# AIAO.net
KiCad netlist of a schematic drawn in Altium Designer
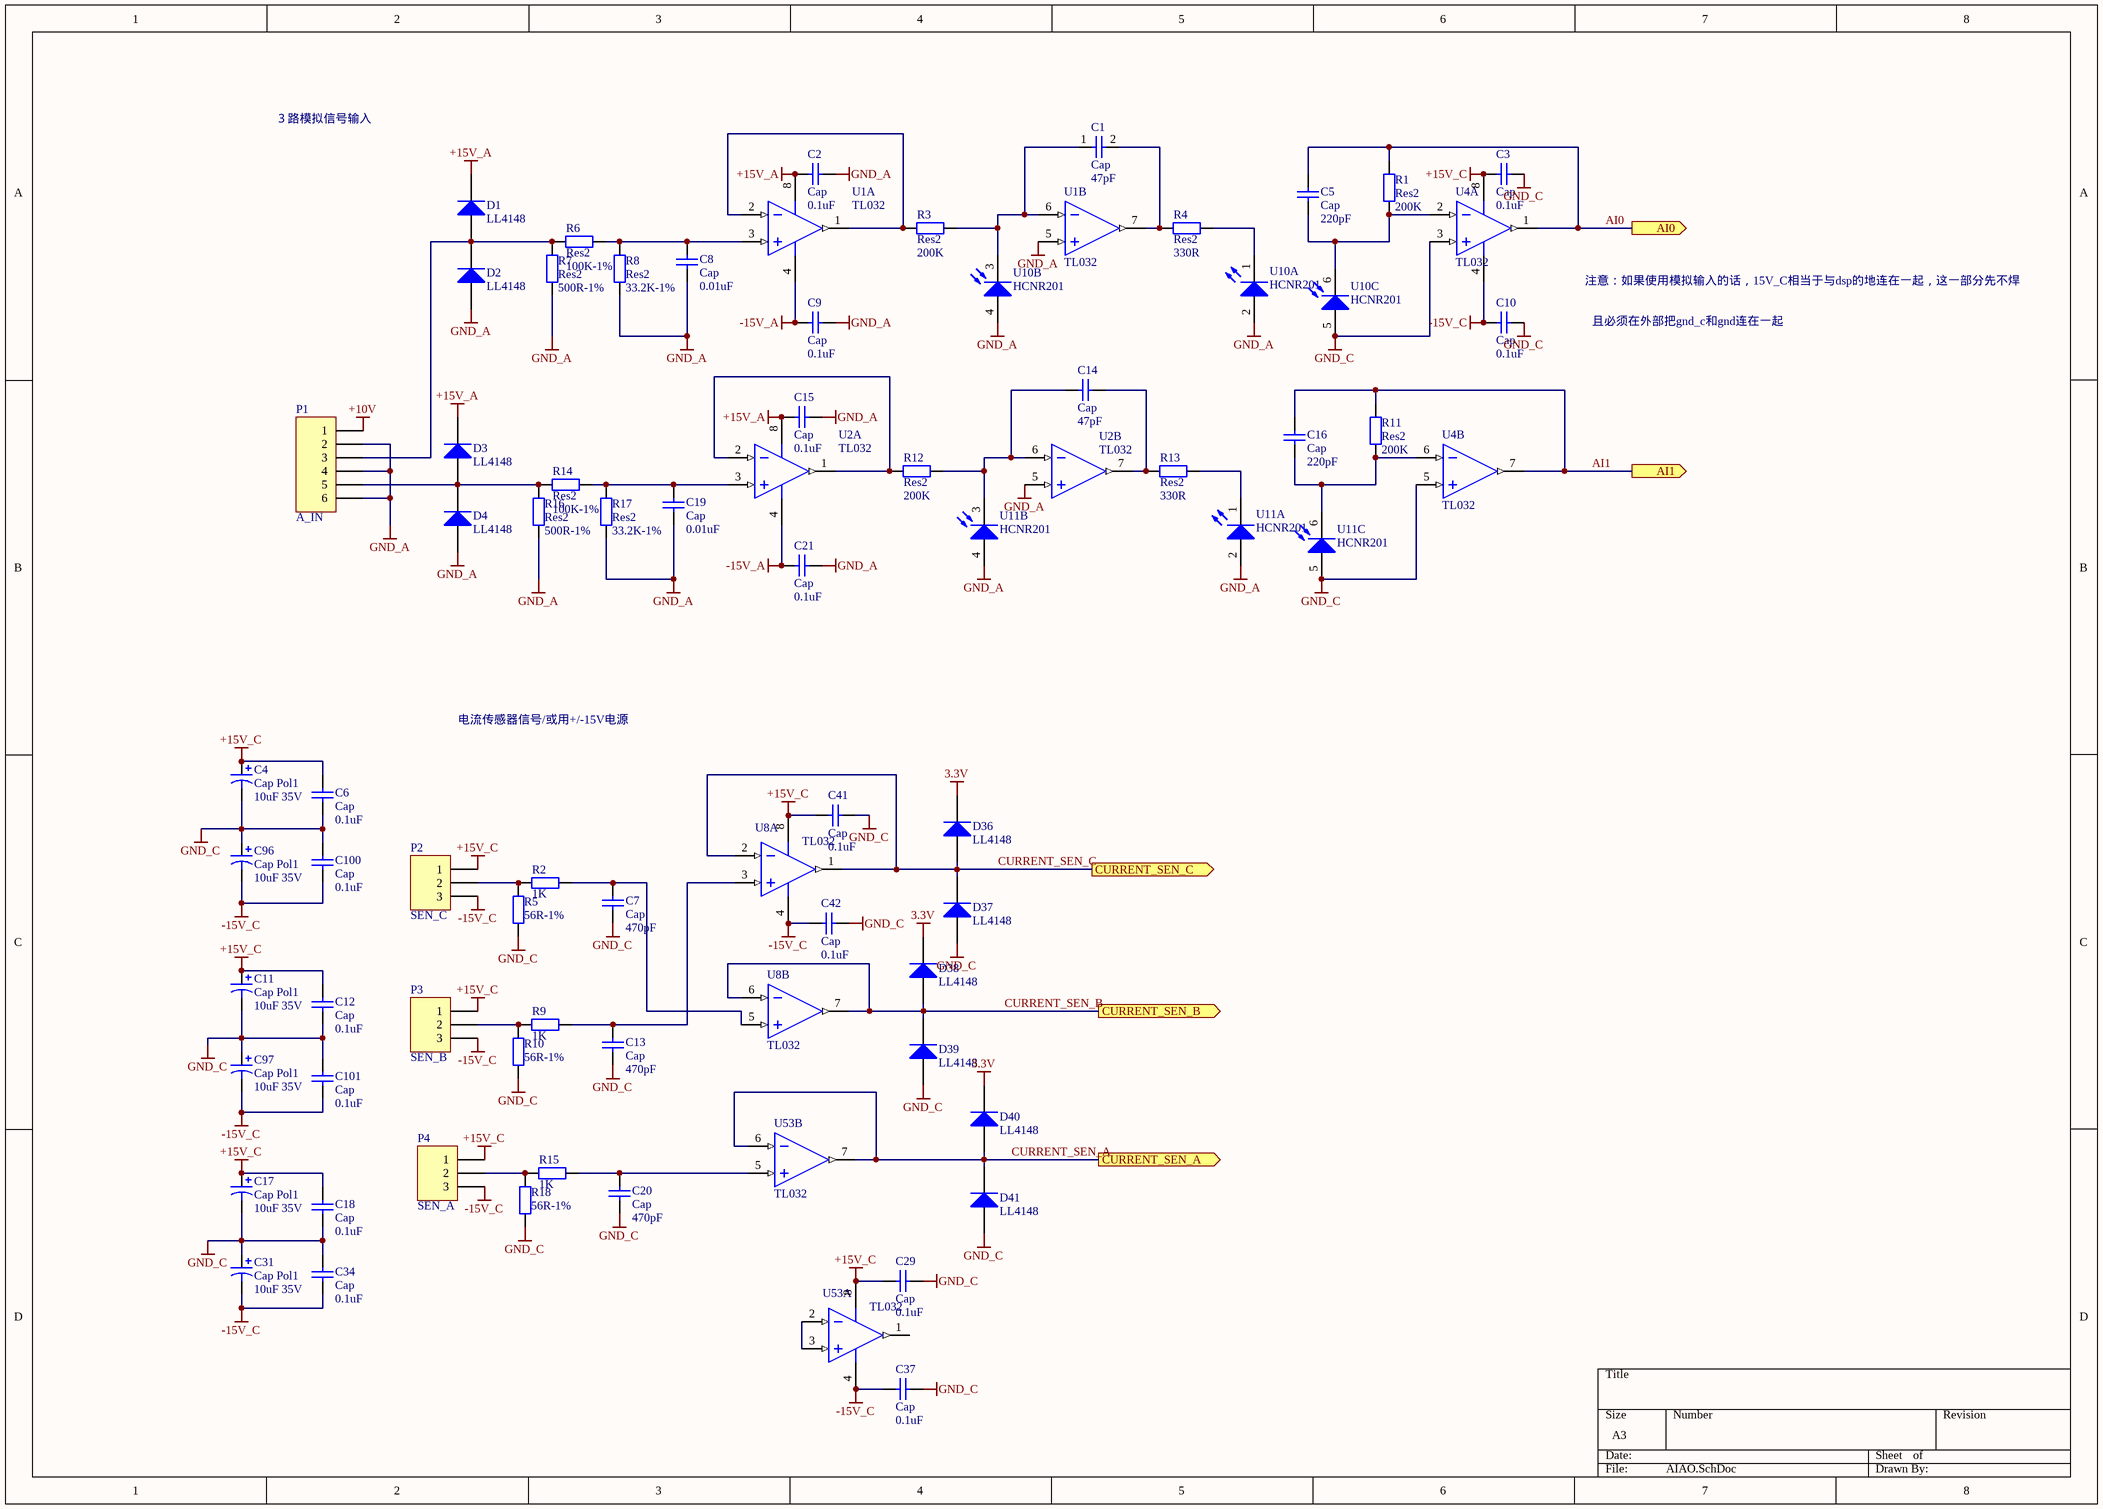
[diagram p0: AIAO.SchDoc]

(export (version "E")
  (design (tool "Eeschema 10.0.6"))
  (components
    (comp (ref "C1")
      (value "Cap")
      (footprint "1206")
      (description "Capacitor")
      (fields (field (name "ALTIUM_VALUE") "47pF") (field (name "PUBLISHER") "Altium Limited"))
      (libsource (lib "") (part "Cap_1"))
    )
    (comp (ref "C2")
      (value "Cap")
      (footprint "1206")
      (description "Capacitor")
      (fields (field (name "ALTIUM_VALUE") "0.1uF") (field (name "PUBLISHER") "Altium Limited"))
      (libsource (lib "Miscellaneous Devices") (part "Cap"))
    )
    (comp (ref "C3")
      (value "Cap")
      (footprint "1206")
      (description "Capacitor")
      (fields (field (name "ALTIUM_VALUE") "0.1uF") (field (name "PUBLISHER") "Altium Limited"))
      (libsource (lib "Miscellaneous Devices") (part "Cap"))
    )
    (comp (ref "C4")
      (value "Cap Pol1")
      (footprint "KEMET Electronics Footprints:1206")
      (description "Polarized Capacitor (Radial)")
      (fields (field (name "ALTIUM_VALUE") "10uF 35V") (field (name "PUBLISHER") "Altium Limited"))
      (libsource (lib "Miscellaneous Devices") (part "Cap Pol1"))
    )
    (comp (ref "C5")
      (value "Cap")
      (footprint "1206")
      (description "Capacitor")
      (fields (field (name "ALTIUM_VALUE") "220pF") (field (name "PUBLISHER") "Altium Limited"))
      (libsource (lib "Miscellaneous Devices") (part "Cap"))
    )
    (comp (ref "C6")
      (value "Cap")
      (footprint "1206")
      (description "Capacitor")
      (fields (field (name "ALTIUM_VALUE") "0.1uF") (field (name "PUBLISHER") "Altium Limited"))
      (libsource (lib "Miscellaneous Devices") (part "Cap"))
    )
    (comp (ref "C7")
      (value "Cap")
      (footprint "1206")
      (description "Capacitor")
      (fields (field (name "ALTIUM_VALUE") "470pF") (field (name "PUBLISHER") "Altium Limited"))
      (libsource (lib "Miscellaneous Devices") (part "Cap"))
    )
    (comp (ref "C8")
      (value "Cap")
      (footprint "1206")
      (description "Capacitor")
      (fields (field (name "ALTIUM_VALUE") "0.01uF") (field (name "PUBLISHER") "Altium Limited"))
      (libsource (lib "Miscellaneous Devices") (part "Cap"))
    )
    (comp (ref "C9")
      (value "Cap")
      (footprint "1206")
      (description "Capacitor")
      (fields (field (name "ALTIUM_VALUE") "0.1uF") (field (name "PUBLISHER") "Altium Limited"))
      (libsource (lib "Miscellaneous Devices") (part "Cap"))
    )
    (comp (ref "C10")
      (value "Cap")
      (footprint "1206")
      (description "Capacitor")
      (fields (field (name "ALTIUM_VALUE") "0.1uF") (field (name "PUBLISHER") "Altium Limited"))
      (libsource (lib "Miscellaneous Devices") (part "Cap"))
    )
    (comp (ref "C11")
      (value "Cap Pol1")
      (footprint "KEMET Electronics Footprints:1206")
      (description "Polarized Capacitor (Radial)")
      (fields (field (name "ALTIUM_VALUE") "10uF 35V") (field (name "PUBLISHER") "Altium Limited"))
      (libsource (lib "Miscellaneous Devices") (part "Cap Pol1"))
    )
    (comp (ref "C12")
      (value "Cap")
      (footprint "1206")
      (description "Capacitor")
      (fields (field (name "ALTIUM_VALUE") "0.1uF") (field (name "PUBLISHER") "Altium Limited"))
      (libsource (lib "Miscellaneous Devices") (part "Cap"))
    )
    (comp (ref "C13")
      (value "Cap")
      (footprint "1206")
      (description "Capacitor")
      (fields (field (name "ALTIUM_VALUE") "470pF") (field (name "PUBLISHER") "Altium Limited"))
      (libsource (lib "Miscellaneous Devices") (part "Cap"))
    )
    (comp (ref "C14")
      (value "Cap")
      (footprint "1206")
      (description "Capacitor")
      (fields (field (name "ALTIUM_VALUE") "47pF") (field (name "PUBLISHER") "Altium Limited"))
      (libsource (lib "Miscellaneous Devices") (part "Cap"))
    )
    (comp (ref "C15")
      (value "Cap")
      (footprint "1206")
      (description "Capacitor")
      (fields (field (name "ALTIUM_VALUE") "0.1uF") (field (name "PUBLISHER") "Altium Limited"))
      (libsource (lib "Miscellaneous Devices") (part "Cap"))
    )
    (comp (ref "C16")
      (value "Cap")
      (footprint "1206")
      (description "Capacitor")
      (fields (field (name "ALTIUM_VALUE") "220pF") (field (name "PUBLISHER") "Altium Limited"))
      (libsource (lib "Miscellaneous Devices") (part "Cap"))
    )
    (comp (ref "C17")
      (value "Cap Pol1")
      (footprint "KEMET Electronics Footprints:1206")
      (description "Polarized Capacitor (Radial)")
      (fields (field (name "ALTIUM_VALUE") "10uF 35V") (field (name "PUBLISHER") "Altium Limited"))
      (libsource (lib "Miscellaneous Devices") (part "Cap Pol1"))
    )
    (comp (ref "C18")
      (value "Cap")
      (footprint "1206")
      (description "Capacitor")
      (fields (field (name "ALTIUM_VALUE") "0.1uF") (field (name "PUBLISHER") "Altium Limited"))
      (libsource (lib "Miscellaneous Devices") (part "Cap"))
    )
    (comp (ref "C19")
      (value "Cap")
      (footprint "1206")
      (description "Capacitor")
      (fields (field (name "ALTIUM_VALUE") "0.01uF") (field (name "PUBLISHER") "Altium Limited"))
      (libsource (lib "Miscellaneous Devices") (part "Cap"))
    )
    (comp (ref "C20")
      (value "Cap")
      (footprint "1206")
      (description "Capacitor")
      (fields (field (name "ALTIUM_VALUE") "470pF") (field (name "PUBLISHER") "Altium Limited"))
      (libsource (lib "Miscellaneous Devices") (part "Cap"))
    )
    (comp (ref "C21")
      (value "Cap")
      (footprint "1206")
      (description "Capacitor")
      (fields (field (name "ALTIUM_VALUE") "0.1uF") (field (name "PUBLISHER") "Altium Limited"))
      (libsource (lib "Miscellaneous Devices") (part "Cap"))
    )
    (comp (ref "C29")
      (value "Cap")
      (footprint "1206")
      (description "Capacitor")
      (fields (field (name "ALTIUM_VALUE") "0.1uF") (field (name "PUBLISHER") "Altium Limited"))
      (libsource (lib "Miscellaneous Devices") (part "Cap"))
    )
    (comp (ref "C31")
      (value "Cap Pol1")
      (footprint "KEMET Electronics Footprints:1206")
      (description "Polarized Capacitor (Radial)")
      (fields (field (name "ALTIUM_VALUE") "10uF 35V") (field (name "PUBLISHER") "Altium Limited"))
      (libsource (lib "Miscellaneous Devices") (part "Cap Pol1"))
    )
    (comp (ref "C34")
      (value "Cap")
      (footprint "1206")
      (description "Capacitor")
      (fields (field (name "ALTIUM_VALUE") "0.1uF") (field (name "PUBLISHER") "Altium Limited"))
      (libsource (lib "Miscellaneous Devices") (part "Cap"))
    )
    (comp (ref "C37")
      (value "Cap")
      (footprint "1206")
      (description "Capacitor")
      (fields (field (name "ALTIUM_VALUE") "0.1uF") (field (name "PUBLISHER") "Altium Limited"))
      (libsource (lib "Miscellaneous Devices") (part "Cap"))
    )
    (comp (ref "C41")
      (value "Cap")
      (footprint "1206")
      (description "Capacitor")
      (fields (field (name "ALTIUM_VALUE") "0.1uF") (field (name "PUBLISHER") "Altium Limited"))
      (libsource (lib "Miscellaneous Devices") (part "Cap"))
    )
    (comp (ref "C42")
      (value "Cap")
      (footprint "1206")
      (description "Capacitor")
      (fields (field (name "ALTIUM_VALUE") "0.1uF") (field (name "PUBLISHER") "Altium Limited"))
      (libsource (lib "Miscellaneous Devices") (part "Cap"))
    )
    (comp (ref "C96")
      (value "Cap Pol1")
      (footprint "KEMET Electronics Footprints:1206")
      (description "Polarized Capacitor (Radial)")
      (fields (field (name "ALTIUM_VALUE") "10uF 35V") (field (name "PUBLISHER") "Altium Limited"))
      (libsource (lib "Miscellaneous Devices") (part "Cap Pol1"))
    )
    (comp (ref "C97")
      (value "Cap Pol1")
      (footprint "KEMET Electronics Footprints:1206")
      (description "Polarized Capacitor (Radial)")
      (fields (field (name "ALTIUM_VALUE") "10uF 35V") (field (name "PUBLISHER") "Altium Limited"))
      (libsource (lib "Miscellaneous Devices") (part "Cap Pol1"))
    )
    (comp (ref "C100")
      (value "Cap")
      (footprint "1206")
      (description "Capacitor")
      (fields (field (name "ALTIUM_VALUE") "0.1uF") (field (name "PUBLISHER") "Altium Limited"))
      (libsource (lib "Miscellaneous Devices") (part "Cap"))
    )
    (comp (ref "C101")
      (value "Cap")
      (footprint "1206")
      (description "Capacitor")
      (fields (field (name "ALTIUM_VALUE") "0.1uF") (field (name "PUBLISHER") "Altium Limited"))
      (libsource (lib "Miscellaneous Devices") (part "Cap"))
    )
    (comp (ref "D1")
      (value "LL4148")
      (footprint "SOD-80/MLL34")
      (description "High Conductance Fast Diode")
      (fields (field (name "PUBLISHER") "Altium Limited"))
      (libsource (lib "Miscellaneous Devices") (part "Diode 1N4148"))
    )
    (comp (ref "D2")
      (value "LL4148")
      (footprint "SOD-80/MLL34")
      (description "High Conductance Fast Diode")
      (fields (field (name "PUBLISHER") "Altium Limited"))
      (libsource (lib "Miscellaneous Devices") (part "Diode 1N4148"))
    )
    (comp (ref "D3")
      (value "LL4148")
      (footprint "SOD-80/MLL34")
      (description "High Conductance Fast Diode")
      (fields (field (name "PUBLISHER") "Altium Limited"))
      (libsource (lib "Miscellaneous Devices") (part "Diode 1N4148"))
    )
    (comp (ref "D4")
      (value "LL4148")
      (footprint "SOD-80/MLL34")
      (description "High Conductance Fast Diode")
      (fields (field (name "PUBLISHER") "Altium Limited"))
      (libsource (lib "Miscellaneous Devices") (part "Diode 1N4148"))
    )
    (comp (ref "D36")
      (value "LL4148")
      (footprint "SOD-80/MLL34")
      (description "1 Amp General Purpose Rectifier")
      (fields (field (name "PUBLISHER") "Altium Limited"))
      (libsource (lib "Miscellaneous Devices") (part "Diode 1N4007"))
    )
    (comp (ref "D37")
      (value "LL4148")
      (footprint "SOD-80/MLL34")
      (description "1 Amp General Purpose Rectifier")
      (fields (field (name "PUBLISHER") "Altium Limited"))
      (libsource (lib "Miscellaneous Devices") (part "Diode 1N4007"))
    )
    (comp (ref "D38")
      (value "LL4148")
      (footprint "SOD-80/MLL34")
      (description "1 Amp General Purpose Rectifier")
      (fields (field (name "PUBLISHER") "Altium Limited"))
      (libsource (lib "Miscellaneous Devices") (part "Diode 1N4007"))
    )
    (comp (ref "D39")
      (value "LL4148")
      (footprint "SOD-80/MLL34")
      (description "1 Amp General Purpose Rectifier")
      (fields (field (name "PUBLISHER") "Altium Limited"))
      (libsource (lib "Miscellaneous Devices") (part "Diode 1N4007"))
    )
    (comp (ref "D40")
      (value "LL4148")
      (footprint "SOD-80/MLL34")
      (description "1 Amp General Purpose Rectifier")
      (fields (field (name "PUBLISHER") "Altium Limited"))
      (libsource (lib "Miscellaneous Devices") (part "Diode 1N4007"))
    )
    (comp (ref "D41")
      (value "LL4148")
      (footprint "SOD-80/MLL34")
      (description "1 Amp General Purpose Rectifier")
      (fields (field (name "PUBLISHER") "Altium Limited"))
      (libsource (lib "Miscellaneous Devices") (part "Diode 1N4007"))
    )
    (comp (ref "P1")
      (value "A_IN")
      (footprint "phenox-6")
      (description "Header, 6-Pin")
      (fields (field (name "PUBLISHER") "Altium Limited"))
      (libsource (lib "Miscellaneous Connectors") (part "Header 6"))
    )
    (comp (ref "P2")
      (value "SEN_C")
      (footprint "PHENOX-3")
      (description "Header, 3-Pin")
      (fields (field (name "PUBLISHER") "Altium Limited"))
      (libsource (lib "Miscellaneous Connectors") (part "Header 3"))
    )
    (comp (ref "P3")
      (value "SEN_B")
      (footprint "PHENOX-3")
      (description "Header, 3-Pin")
      (fields (field (name "PUBLISHER") "Altium Limited"))
      (libsource (lib "Miscellaneous Connectors") (part "Header 3"))
    )
    (comp (ref "P4")
      (value "SEN_A")
      (footprint "PHENOX-3")
      (description "Header, 3-Pin")
      (fields (field (name "PUBLISHER") "Altium Limited"))
      (libsource (lib "Miscellaneous Connectors") (part "Header 3"))
    )
    (comp (ref "R1")
      (value "Res2")
      (footprint "1206")
      (description "Resistor")
      (fields (field (name "ALTIUM_VALUE") "200K") (field (name "PUBLISHER") "Altium Limited"))
      (libsource (lib "Miscellaneous Devices") (part "Res2"))
    )
    (comp (ref "R2")
      (value "1K")
      (footprint "1206")
      (description "Resistor")
      (fields (field (name "Comment") "Res2") (field (name "PUBLISHER") "Altium Limited"))
      (libsource (lib "") (part "Res2_1"))
    )
    (comp (ref "R3")
      (value "Res2")
      (footprint "1206")
      (description "Resistor")
      (fields (field (name "ALTIUM_VALUE") "200K") (field (name "PUBLISHER") "Altium Limited"))
      (libsource (lib "") (part "Res2_1"))
    )
    (comp (ref "R4")
      (value "Res2")
      (footprint "1206")
      (description "Resistor")
      (fields (field (name "ALTIUM_VALUE") "330R") (field (name "PUBLISHER") "Altium Limited"))
      (libsource (lib "") (part "Res2_1"))
    )
    (comp (ref "R5")
      (value "56R-1%")
      (footprint "1206")
      (description "Resistor")
      (fields (field (name "Comment") "Res2") (field (name "PUBLISHER") "Altium Limited"))
      (libsource (lib "Miscellaneous Devices") (part "Res2"))
    )
    (comp (ref "R6")
      (value "Res2")
      (footprint "1206")
      (description "Resistor")
      (fields (field (name "ALTIUM_VALUE") "100K-1%") (field (name "PUBLISHER") "Altium Limited"))
      (libsource (lib "") (part "Res2_1"))
    )
    (comp (ref "R7")
      (value "Res2")
      (footprint "1206")
      (description "Resistor")
      (fields (field (name "ALTIUM_VALUE") "500R-1%") (field (name "PUBLISHER") "Altium Limited"))
      (libsource (lib "Miscellaneous Devices") (part "Res2"))
    )
    (comp (ref "R8")
      (value "Res2")
      (footprint "1206")
      (description "Resistor")
      (fields (field (name "ALTIUM_VALUE") "33.2K-1%") (field (name "PUBLISHER") "Altium Limited"))
      (libsource (lib "Miscellaneous Devices") (part "Res2"))
    )
    (comp (ref "R9")
      (value "1K")
      (footprint "1206")
      (description "Resistor")
      (fields (field (name "Comment") "Res2") (field (name "PUBLISHER") "Altium Limited"))
      (libsource (lib "") (part "Res2_1"))
    )
    (comp (ref "R10")
      (value "56R-1%")
      (footprint "1206")
      (description "Resistor")
      (fields (field (name "Comment") "Res2") (field (name "PUBLISHER") "Altium Limited"))
      (libsource (lib "Miscellaneous Devices") (part "Res2"))
    )
    (comp (ref "R11")
      (value "Res2")
      (footprint "1206")
      (description "Resistor")
      (fields (field (name "ALTIUM_VALUE") "200K") (field (name "PUBLISHER") "Altium Limited"))
      (libsource (lib "Miscellaneous Devices") (part "Res2"))
    )
    (comp (ref "R12")
      (value "Res2")
      (footprint "1206")
      (description "Resistor")
      (fields (field (name "ALTIUM_VALUE") "200K") (field (name "PUBLISHER") "Altium Limited"))
      (libsource (lib "") (part "Res2_1"))
    )
    (comp (ref "R13")
      (value "Res2")
      (footprint "1206")
      (description "Resistor")
      (fields (field (name "ALTIUM_VALUE") "330R") (field (name "PUBLISHER") "Altium Limited"))
      (libsource (lib "") (part "Res2_1"))
    )
    (comp (ref "R14")
      (value "Res2")
      (footprint "1206")
      (description "Resistor")
      (fields (field (name "ALTIUM_VALUE") "100K-1%") (field (name "PUBLISHER") "Altium Limited"))
      (libsource (lib "") (part "Res2_1"))
    )
    (comp (ref "R15")
      (value "1K")
      (footprint "1206")
      (description "Resistor")
      (fields (field (name "Comment") "Res2") (field (name "PUBLISHER") "Altium Limited"))
      (libsource (lib "") (part "Res2_1"))
    )
    (comp (ref "R16")
      (value "Res2")
      (footprint "1206")
      (description "Resistor")
      (fields (field (name "ALTIUM_VALUE") "500R-1%") (field (name "PUBLISHER") "Altium Limited"))
      (libsource (lib "Miscellaneous Devices") (part "Res2"))
    )
    (comp (ref "R17")
      (value "Res2")
      (footprint "1206")
      (description "Resistor")
      (fields (field (name "ALTIUM_VALUE") "33.2K-1%") (field (name "PUBLISHER") "Altium Limited"))
      (libsource (lib "Miscellaneous Devices") (part "Res2"))
    )
    (comp (ref "R18")
      (value "56R-1%")
      (footprint "1206")
      (description "Resistor")
      (fields (field (name "Comment") "Res2") (field (name "PUBLISHER") "Altium Limited"))
      (libsource (lib "Miscellaneous Devices") (part "Res2"))
    )
    (comp (ref "U1") (value "TL032") (footprint "SO-8") (libsource (lib "Schlib1") (part "TL032")))
    (comp (ref "U2") (value "TL032") (footprint "SO-8") (libsource (lib "Schlib1") (part "TL032")))
    (comp (ref "U4") (value "TL032") (footprint "SO-8") (libsource (lib "Schlib1") (part "TL032")))
    (comp (ref "U8") (value "TL032") (footprint "SO-8") (libsource (lib "Schlib1") (part "TL032")))
    (comp (ref "U10")
      (value "HCNR201")
      (footprint "SOP254P1230X400-8N-2")
      (libsource (lib "Schlib2") (part "HCNR201"))
    )
    (comp (ref "U11")
      (value "HCNR201")
      (footprint "SOP254P1230X400-8N-2")
      (libsource (lib "Schlib2") (part "HCNR201"))
    )
    (comp (ref "U53") (value "TL032") (footprint "SO-8") (libsource (lib "Schlib1") (part "TL032")))
  )
  (nets
    (net (code "1") (name "+10V") (class "Default")
      (node (ref "P1") (pin "1") (pinfunction "1_1") (pintype "passive"))
    )
    (net (code "2") (name "+15V_A") (class "Default")
      (node (ref "C15") (pin "1") (pinfunction "1_1") (pintype "passive"))
      (node (ref "C2") (pin "1") (pinfunction "1_1") (pintype "passive"))
      (node (ref "D1") (pin "2") (pinfunction "K_2") (pintype "passive"))
      (node (ref "D3") (pin "2") (pinfunction "K_2") (pintype "passive"))
      (node (ref "U1") (pin "8") (pinfunction "V+_8") (pintype "power_in"))
      (node (ref "U2") (pin "8") (pinfunction "V+_8") (pintype "power_in"))
    )
    (net (code "3") (name "+15V_C") (class "Default")
      (node (ref "C11") (pin "1") (pinfunction "1_1") (pintype "passive"))
      (node (ref "C12") (pin "2") (pinfunction "2_2") (pintype "passive"))
      (node (ref "C17") (pin "1") (pinfunction "1_1") (pintype "passive"))
      (node (ref "C18") (pin "2") (pinfunction "2_2") (pintype "passive"))
      (node (ref "C29") (pin "2") (pinfunction "2_2") (pintype "passive"))
      (node (ref "C3") (pin "1") (pinfunction "1_1") (pintype "passive"))
      (node (ref "C4") (pin "1") (pinfunction "1_1") (pintype "passive"))
      (node (ref "C41") (pin "2") (pinfunction "2_2") (pintype "passive"))
      (node (ref "C6") (pin "2") (pinfunction "2_2") (pintype "passive"))
      (node (ref "P2") (pin "1") (pinfunction "1_1") (pintype "passive"))
      (node (ref "P3") (pin "1") (pinfunction "1_1") (pintype "passive"))
      (node (ref "P4") (pin "1") (pinfunction "1_1") (pintype "passive"))
      (node (ref "U4") (pin "8") (pinfunction "V+_8") (pintype "power_in"))
      (node (ref "U53") (pin "8") (pinfunction "V+_8") (pintype "power_in"))
      (node (ref "U8") (pin "8") (pinfunction "V+_8") (pintype "power_in"))
    )
    (net (code "4") (name "-15V_A") (class "Default")
      (node (ref "C21") (pin "1") (pinfunction "1_1") (pintype "passive"))
      (node (ref "C9") (pin "1") (pinfunction "1_1") (pintype "passive"))
      (node (ref "U1") (pin "4") (pinfunction "V-_4") (pintype "power_in"))
      (node (ref "U2") (pin "4") (pinfunction "V-_4") (pintype "power_in"))
    )
    (net (code "5") (name "-15V_C") (class "Default")
      (node (ref "C10") (pin "1") (pinfunction "1_1") (pintype "passive"))
      (node (ref "C100") (pin "1") (pinfunction "1_1") (pintype "passive"))
      (node (ref "C101") (pin "1") (pinfunction "1_1") (pintype "passive"))
      (node (ref "C31") (pin "2") (pinfunction "2_2") (pintype "passive"))
      (node (ref "C34") (pin "1") (pinfunction "1_1") (pintype "passive"))
      (node (ref "C37") (pin "2") (pinfunction "2_2") (pintype "passive"))
      (node (ref "C42") (pin "2") (pinfunction "2_2") (pintype "passive"))
      (node (ref "C96") (pin "2") (pinfunction "2_2") (pintype "passive"))
      (node (ref "C97") (pin "2") (pinfunction "2_2") (pintype "passive"))
      (node (ref "P2") (pin "3") (pinfunction "3_3") (pintype "passive"))
      (node (ref "P3") (pin "3") (pinfunction "3_3") (pintype "passive"))
      (node (ref "P4") (pin "3") (pinfunction "3_3") (pintype "passive"))
      (node (ref "U4") (pin "4") (pinfunction "V-_4") (pintype "power_in"))
      (node (ref "U53") (pin "4") (pinfunction "V-_4") (pintype "power_in"))
      (node (ref "U8") (pin "4") (pinfunction "V-_4") (pintype "power_in"))
    )
    (net (code "6") (name "/AI0") (class "Default")
      (node (ref "C5") (pin "2") (pinfunction "2_2") (pintype "passive"))
      (node (ref "R1") (pin "2") (pinfunction "2_2") (pintype "passive"))
      (node (ref "U4") (pin "1") (pinfunction "OUT_1") (pintype "output"))
    )
    (net (code "7") (name "/AI1") (class "Default")
      (node (ref "C16") (pin "2") (pinfunction "2_2") (pintype "passive"))
      (node (ref "R11") (pin "2") (pinfunction "2_2") (pintype "passive"))
      (node (ref "U4") (pin "7") (pinfunction "OUT_7") (pintype "output"))
    )
    (net (code "8") (name "/CURRENT_SEN_A") (class "Default")
      (node (ref "D40") (pin "1") (pinfunction "A_1") (pintype "passive"))
      (node (ref "D41") (pin "2") (pinfunction "K_2") (pintype "passive"))
      (node (ref "U53") (pin "6") (pinfunction "IN-_6") (pintype "input"))
      (node (ref "U53") (pin "7") (pinfunction "OUT_7") (pintype "output"))
    )
    (net (code "9") (name "/CURRENT_SEN_B") (class "Default")
      (node (ref "D38") (pin "1") (pinfunction "A_1") (pintype "passive"))
      (node (ref "D39") (pin "2") (pinfunction "K_2") (pintype "passive"))
      (node (ref "U8") (pin "6") (pinfunction "IN-_6") (pintype "input"))
      (node (ref "U8") (pin "7") (pinfunction "OUT_7") (pintype "output"))
    )
    (net (code "10") (name "/CURRENT_SEN_C") (class "Default")
      (node (ref "D36") (pin "1") (pinfunction "A_1") (pintype "passive"))
      (node (ref "D37") (pin "2") (pinfunction "K_2") (pintype "passive"))
      (node (ref "U8") (pin "1") (pinfunction "OUT_1") (pintype "output"))
      (node (ref "U8") (pin "2") (pinfunction "IN-_2") (pintype "input"))
    )
    (net (code "11") (name "3.3V") (class "Default")
      (node (ref "D36") (pin "2") (pinfunction "K_2") (pintype "passive"))
      (node (ref "D38") (pin "2") (pinfunction "K_2") (pintype "passive"))
      (node (ref "D40") (pin "2") (pinfunction "K_2") (pintype "passive"))
    )
    (net (code "12") (name "GND_A") (class "Default")
      (node (ref "C15") (pin "2") (pinfunction "2_2") (pintype "passive"))
      (node (ref "C19") (pin "1") (pinfunction "1_1") (pintype "passive"))
      (node (ref "C2") (pin "2") (pinfunction "2_2") (pintype "passive"))
      (node (ref "C21") (pin "2") (pinfunction "2_2") (pintype "passive"))
      (node (ref "C8") (pin "1") (pinfunction "1_1") (pintype "passive"))
      (node (ref "C9") (pin "2") (pinfunction "2_2") (pintype "passive"))
      (node (ref "D2") (pin "1") (pinfunction "A_1") (pintype "passive"))
      (node (ref "D4") (pin "1") (pinfunction "A_1") (pintype "passive"))
      (node (ref "P1") (pin "2") (pinfunction "2_2") (pintype "passive"))
      (node (ref "P1") (pin "4") (pinfunction "4_4") (pintype "passive"))
      (node (ref "P1") (pin "6") (pinfunction "6_6") (pintype "passive"))
      (node (ref "R16") (pin "1") (pinfunction "1_1") (pintype "passive"))
      (node (ref "R17") (pin "1") (pinfunction "1_1") (pintype "passive"))
      (node (ref "R7") (pin "1") (pinfunction "1_1") (pintype "passive"))
      (node (ref "R8") (pin "1") (pinfunction "1_1") (pintype "passive"))
      (node (ref "U1") (pin "5") (pinfunction "IN+_5") (pintype "input"))
      (node (ref "U10") (pin "2") (pinfunction "A_2") (pintype "passive"))
      (node (ref "U10") (pin "4") (pinfunction "A_4") (pintype "passive"))
      (node (ref "U11") (pin "2") (pinfunction "A_2") (pintype "passive"))
      (node (ref "U11") (pin "4") (pinfunction "A_4") (pintype "passive"))
      (node (ref "U2") (pin "5") (pinfunction "IN+_5") (pintype "input"))
    )
    (net (code "13") (name "GND_C") (class "Default")
      (node (ref "C10") (pin "2") (pinfunction "2_2") (pintype "passive"))
      (node (ref "C100") (pin "2") (pinfunction "2_2") (pintype "passive"))
      (node (ref "C101") (pin "2") (pinfunction "2_2") (pintype "passive"))
      (node (ref "C11") (pin "2") (pinfunction "2_2") (pintype "passive"))
      (node (ref "C12") (pin "1") (pinfunction "1_1") (pintype "passive"))
      (node (ref "C13") (pin "1") (pinfunction "1_1") (pintype "passive"))
      (node (ref "C17") (pin "2") (pinfunction "2_2") (pintype "passive"))
      (node (ref "C18") (pin "1") (pinfunction "1_1") (pintype "passive"))
      (node (ref "C20") (pin "1") (pinfunction "1_1") (pintype "passive"))
      (node (ref "C29") (pin "1") (pinfunction "1_1") (pintype "passive"))
      (node (ref "C3") (pin "2") (pinfunction "2_2") (pintype "passive"))
      (node (ref "C31") (pin "1") (pinfunction "1_1") (pintype "passive"))
      (node (ref "C34") (pin "2") (pinfunction "2_2") (pintype "passive"))
      (node (ref "C37") (pin "1") (pinfunction "1_1") (pintype "passive"))
      (node (ref "C4") (pin "2") (pinfunction "2_2") (pintype "passive"))
      (node (ref "C41") (pin "1") (pinfunction "1_1") (pintype "passive"))
      (node (ref "C42") (pin "1") (pinfunction "1_1") (pintype "passive"))
      (node (ref "C6") (pin "1") (pinfunction "1_1") (pintype "passive"))
      (node (ref "C7") (pin "1") (pinfunction "1_1") (pintype "passive"))
      (node (ref "C96") (pin "1") (pinfunction "1_1") (pintype "passive"))
      (node (ref "C97") (pin "1") (pinfunction "1_1") (pintype "passive"))
      (node (ref "D37") (pin "1") (pinfunction "A_1") (pintype "passive"))
      (node (ref "D39") (pin "1") (pinfunction "A_1") (pintype "passive"))
      (node (ref "D41") (pin "1") (pinfunction "A_1") (pintype "passive"))
      (node (ref "R10") (pin "1") (pinfunction "1_1") (pintype "passive"))
      (node (ref "R18") (pin "1") (pinfunction "1_1") (pintype "passive"))
      (node (ref "R5") (pin "1") (pinfunction "1_1") (pintype "passive"))
      (node (ref "U10") (pin "5") (pinfunction "A_5") (pintype "passive"))
      (node (ref "U11") (pin "5") (pinfunction "A_5") (pintype "passive"))
      (node (ref "U4") (pin "3") (pinfunction "IN+_3") (pintype "input"))
      (node (ref "U4") (pin "5") (pinfunction "IN+_5") (pintype "input"))
    )
    (net (code "14") (name "Net-(D1-A)") (class "Default")
      (node (ref "D1") (pin "1") (pinfunction "A_1") (pintype "passive"))
      (node (ref "D2") (pin "2") (pinfunction "K_2") (pintype "passive"))
      (node (ref "P1") (pin "3") (pinfunction "3_3") (pintype "passive"))
      (node (ref "R6") (pin "1") (pinfunction "1_1") (pintype "passive"))
      (node (ref "R7") (pin "2") (pinfunction "2_2") (pintype "passive"))
    )
    (net (code "15") (name "Net-(D3-A)") (class "Default")
      (node (ref "D3") (pin "1") (pinfunction "A_1") (pintype "passive"))
      (node (ref "D4") (pin "2") (pinfunction "K_2") (pintype "passive"))
      (node (ref "P1") (pin "5") (pinfunction "5_5") (pintype "passive"))
      (node (ref "R14") (pin "1") (pinfunction "1_1") (pintype "passive"))
      (node (ref "R16") (pin "2") (pinfunction "2_2") (pintype "passive"))
    )
    (net (code "16") (name "Net-(P2-Pad2)") (class "Default")
      (node (ref "P2") (pin "2") (pinfunction "2_2") (pintype "passive"))
      (node (ref "R2") (pin "1") (pinfunction "1_1") (pintype "passive"))
      (node (ref "R5") (pin "2") (pinfunction "2_2") (pintype "passive"))
    )
    (net (code "17") (name "Net-(P3-Pad2)") (class "Default")
      (node (ref "P3") (pin "2") (pinfunction "2_2") (pintype "passive"))
      (node (ref "R10") (pin "2") (pinfunction "2_2") (pintype "passive"))
      (node (ref "R9") (pin "1") (pinfunction "1_1") (pintype "passive"))
    )
    (net (code "18") (name "Net-(P4-Pad2)") (class "Default")
      (node (ref "P4") (pin "2") (pinfunction "2_2") (pintype "passive"))
      (node (ref "R15") (pin "1") (pinfunction "1_1") (pintype "passive"))
      (node (ref "R18") (pin "2") (pinfunction "2_2") (pintype "passive"))
    )
    (net (code "19") (name "Net-(U1A-IN+)") (class "Default")
      (node (ref "C8") (pin "2") (pinfunction "2_2") (pintype "passive"))
      (node (ref "R6") (pin "2") (pinfunction "2_2") (pintype "passive"))
      (node (ref "R8") (pin "2") (pinfunction "2_2") (pintype "passive"))
      (node (ref "U1") (pin "3") (pinfunction "IN+_3") (pintype "input"))
    )
    (net (code "20") (name "Net-(U1A-IN-)") (class "Default")
      (node (ref "R3") (pin "1") (pinfunction "1_1") (pintype "passive"))
      (node (ref "U1") (pin "1") (pinfunction "OUT_1") (pintype "output"))
      (node (ref "U1") (pin "2") (pinfunction "IN-_2") (pintype "input"))
    )
    (net (code "21") (name "Net-(U1B-OUT)") (class "Default")
      (node (ref "C1") (pin "2") (pinfunction "2_2") (pintype "passive"))
      (node (ref "R4") (pin "1") (pinfunction "1_1") (pintype "passive"))
      (node (ref "U1") (pin "7") (pinfunction "OUT_7") (pintype "output"))
    )
    (net (code "22") (name "Net-(U2A-IN+)") (class "Default")
      (node (ref "C19") (pin "2") (pinfunction "2_2") (pintype "passive"))
      (node (ref "R14") (pin "2") (pinfunction "2_2") (pintype "passive"))
      (node (ref "R17") (pin "2") (pinfunction "2_2") (pintype "passive"))
      (node (ref "U2") (pin "3") (pinfunction "IN+_3") (pintype "input"))
    )
    (net (code "23") (name "Net-(U2A-IN-)") (class "Default")
      (node (ref "R12") (pin "1") (pinfunction "1_1") (pintype "passive"))
      (node (ref "U2") (pin "1") (pinfunction "OUT_1") (pintype "output"))
      (node (ref "U2") (pin "2") (pinfunction "IN-_2") (pintype "input"))
    )
    (net (code "24") (name "Net-(U2B-OUT)") (class "Default")
      (node (ref "C14") (pin "2") (pinfunction "2_2") (pintype "passive"))
      (node (ref "R13") (pin "1") (pinfunction "1_1") (pintype "passive"))
      (node (ref "U2") (pin "7") (pinfunction "OUT_7") (pintype "output"))
    )
    (net (code "25") (name "Net-(U8A-IN+)") (class "Default")
      (node (ref "C13") (pin "2") (pinfunction "2_2") (pintype "passive"))
      (node (ref "R9") (pin "2") (pinfunction "2_2") (pintype "passive"))
      (node (ref "U8") (pin "3") (pinfunction "IN+_3") (pintype "input"))
    )
    (net (code "26") (name "Net-(U8B-IN+)") (class "Default")
      (node (ref "C7") (pin "2") (pinfunction "2_2") (pintype "passive"))
      (node (ref "R2") (pin "2") (pinfunction "2_2") (pintype "passive"))
      (node (ref "U8") (pin "5") (pinfunction "IN+_5") (pintype "input"))
    )
    (net (code "27") (name "Net-(U10A-K)") (class "Default")
      (node (ref "R4") (pin "2") (pinfunction "2_2") (pintype "passive"))
      (node (ref "U10") (pin "1") (pinfunction "K_1") (pintype "passive"))
    )
    (net (code "28") (name "Net-(U10B-K)") (class "Default")
      (node (ref "C1") (pin "1") (pinfunction "1_1") (pintype "passive"))
      (node (ref "R3") (pin "2") (pinfunction "2_2") (pintype "passive"))
      (node (ref "U1") (pin "6") (pinfunction "IN-_6") (pintype "input"))
      (node (ref "U10") (pin "3") (pinfunction "K_3") (pintype "passive"))
    )
    (net (code "29") (name "Net-(U10C-K)") (class "Default")
      (node (ref "C5") (pin "1") (pinfunction "1_1") (pintype "passive"))
      (node (ref "R1") (pin "1") (pinfunction "1_1") (pintype "passive"))
      (node (ref "U10") (pin "6") (pinfunction "K_6") (pintype "passive"))
      (node (ref "U4") (pin "2") (pinfunction "IN-_2") (pintype "input"))
    )
    (net (code "30") (name "Net-(U11A-K)") (class "Default")
      (node (ref "R13") (pin "2") (pinfunction "2_2") (pintype "passive"))
      (node (ref "U11") (pin "1") (pinfunction "K_1") (pintype "passive"))
    )
    (net (code "31") (name "Net-(U11B-K)") (class "Default")
      (node (ref "C14") (pin "1") (pinfunction "1_1") (pintype "passive"))
      (node (ref "R12") (pin "2") (pinfunction "2_2") (pintype "passive"))
      (node (ref "U11") (pin "3") (pinfunction "K_3") (pintype "passive"))
      (node (ref "U2") (pin "6") (pinfunction "IN-_6") (pintype "input"))
    )
    (net (code "32") (name "Net-(U11C-K)") (class "Default")
      (node (ref "C16") (pin "1") (pinfunction "1_1") (pintype "passive"))
      (node (ref "R11") (pin "1") (pinfunction "1_1") (pintype "passive"))
      (node (ref "U11") (pin "6") (pinfunction "K_6") (pintype "passive"))
      (node (ref "U4") (pin "6") (pinfunction "IN-_6") (pintype "input"))
    )
    (net (code "33") (name "Net-(U53A-IN+)") (class "Default")
      (node (ref "U53") (pin "2") (pinfunction "IN-_2") (pintype "input"))
      (node (ref "U53") (pin "3") (pinfunction "IN+_3") (pintype "input"))
    )
    (net (code "34") (name "Net-(U53B-IN+)") (class "Default")
      (node (ref "C20") (pin "2") (pinfunction "2_2") (pintype "passive"))
      (node (ref "R15") (pin "2") (pinfunction "2_2") (pintype "passive"))
      (node (ref "U53") (pin "5") (pinfunction "IN+_5") (pintype "input"))
    )
    (net (code "35") (name "unconnected-(U53A-OUT-Pad1)") (class "Default")
      (node (ref "U53") (pin "1") (pinfunction "OUT_1") (pintype "output"))
    )
  )
)
